# -_PSU_v2.net
KiCad netlist of a schematic drawn in EAGLE
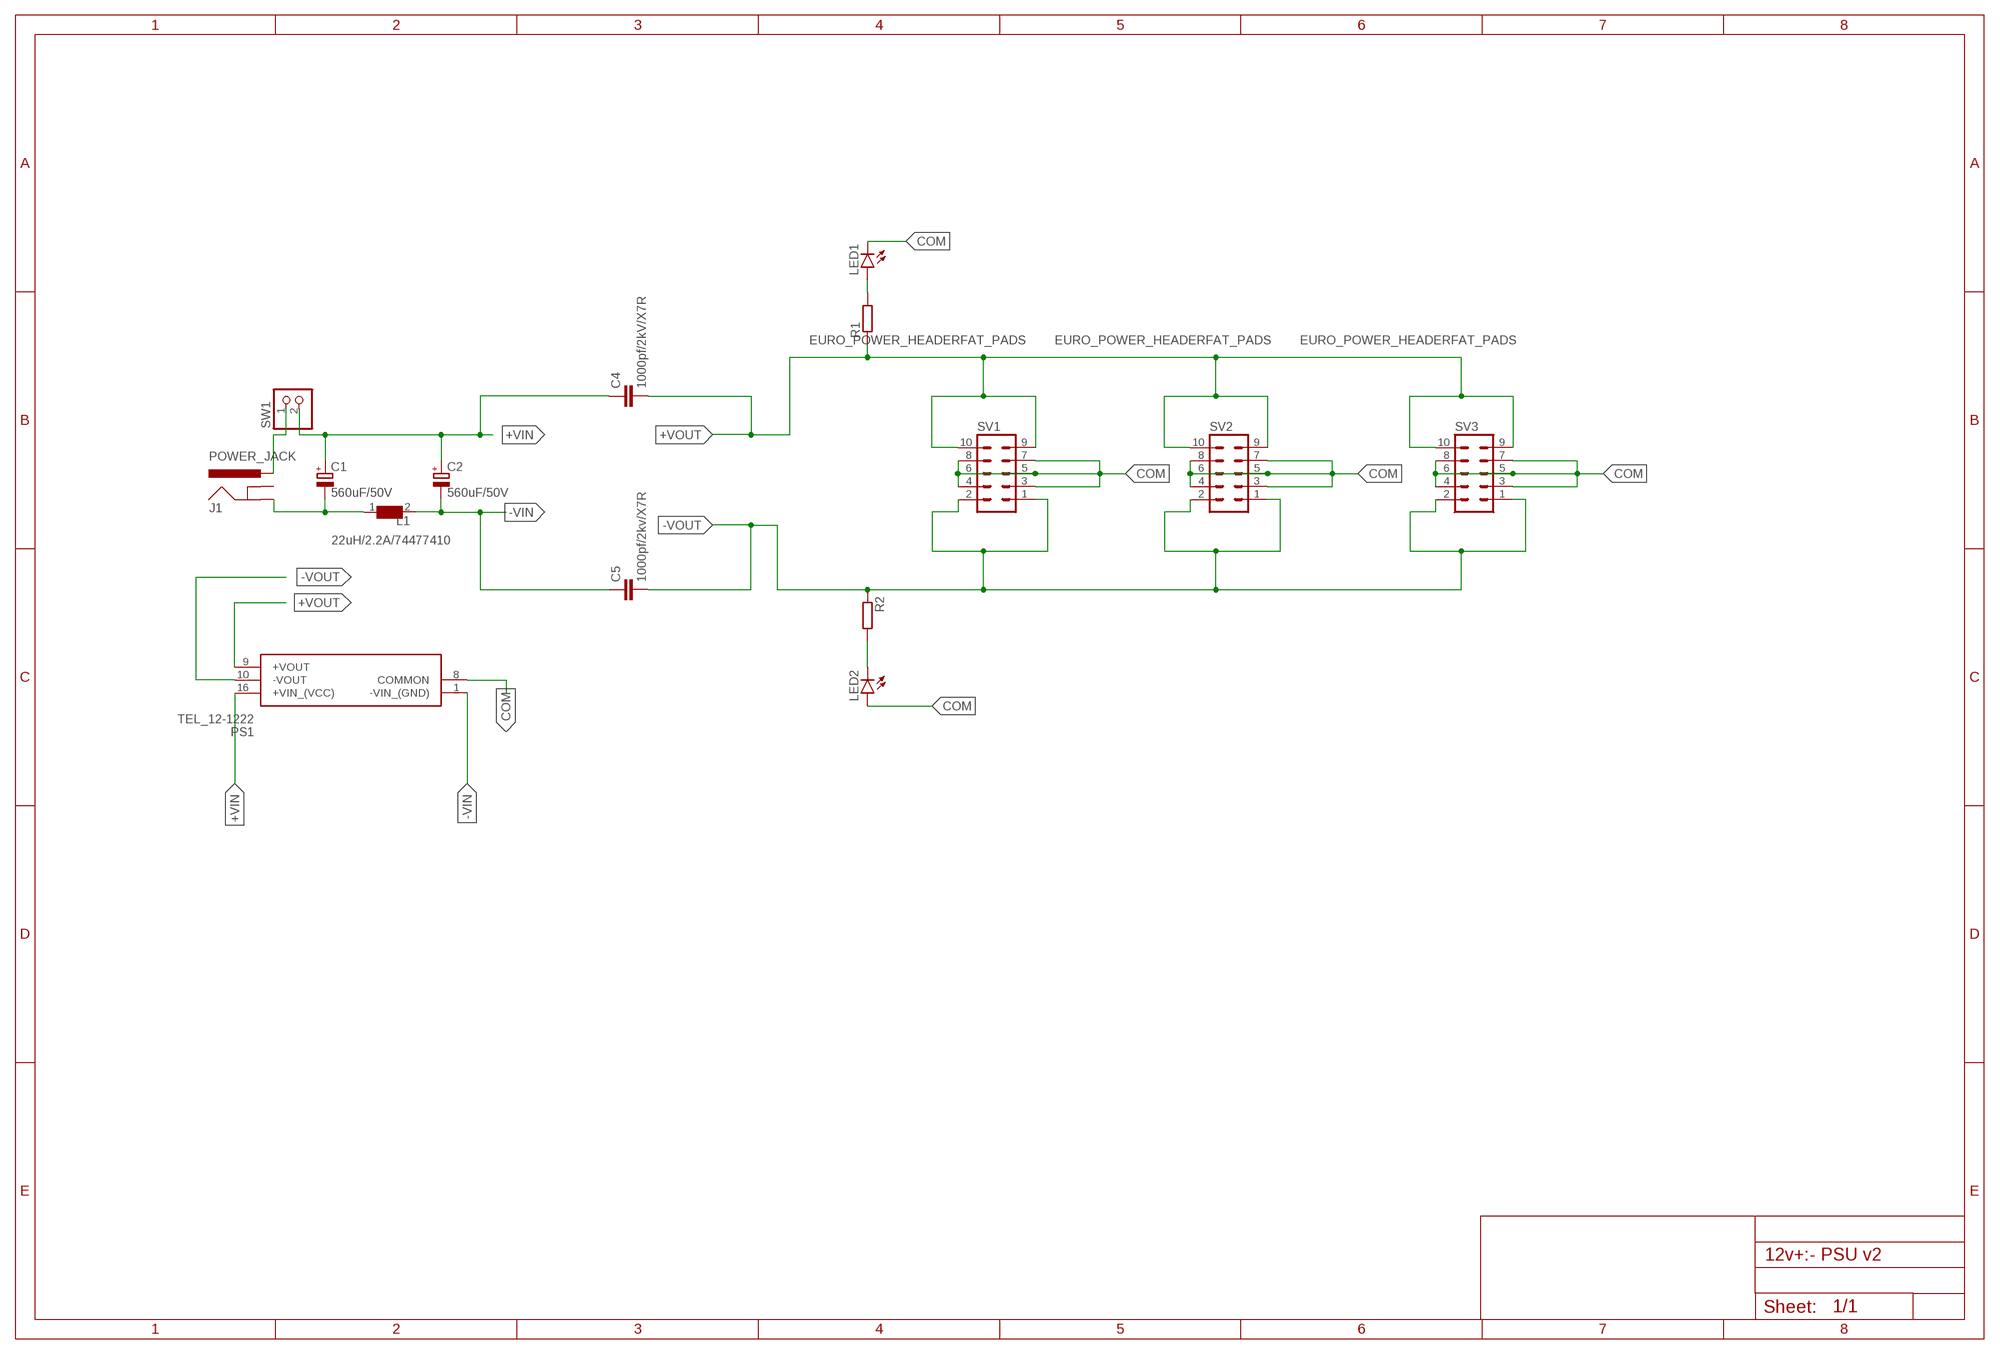
[diagram p0: schematic, sheet 1]

(export (version "E")
  (design (tool "Eeschema 10.0.6"))
  (components
    (comp (ref "C1")
      (value "560uF/50V")
      (footprint "eagle-import:E7,5-16")
      (libsource (lib "eagle-import") (part "CPOL-EUE7.5-16"))
    )
    (comp (ref "C2")
      (value "560uF/50V")
      (footprint "eagle-import:E7,5-16")
      (libsource (lib "eagle-import") (part "CPOL-EUE7.5-16"))
    )
    (comp (ref "C4")
      (value "1000pf/2kV/X7R")
      (footprint "eagle-import:C1808")
      (libsource (lib "eagle-import") (part "C-EUC1808"))
    )
    (comp (ref "C5")
      (value "1000pf/2kv/X7R")
      (footprint "eagle-import:C1808")
      (libsource (lib "eagle-import") (part "C-EUC1808"))
    )
    (comp (ref "J1")
      (value "POWER_JACK")
      (footprint "eagle-import:POWER_JACK_PTH")
      (libsource (lib "eagle-import") (part "POWER_JACK"))
    )
    (comp (ref "L1")
      (value "22uH/2.2A/74477410")
      (footprint "eagle-import:WE-PD2_5848_5820")
      (fields (field (name "MPN") "74477410"))
      (libsource (lib "eagle-import") (part "WE-PD2_5848/5820-74477410"))
    )
    (comp (ref "LED1")
      (value "LED3MM")
      (footprint "eagle-import:LED3MM")
      (libsource (lib "eagle-import") (part "LED3MM"))
    )
    (comp (ref "LED2")
      (value "LED3MM")
      (footprint "eagle-import:LED3MM")
      (libsource (lib "eagle-import") (part "LED3MM"))
    )
    (comp (ref "PS1")
      (value "TEL_12-1222")
      (footprint "eagle-import:TEL121222")
      (fields
        (field (name "MANUFACTURER_PART_NUMBER") "TEL 12-1222")
        (field (name "MOUSER_PART_NUMBER") "495-TEL12-1222")
      )
      (libsource (lib "eagle-import") (part "TEL_12-1222"))
    )
    (comp (ref "R1")
      (value "RESISTOR7MM")
      (footprint "eagle-import:7MM_RESISTOR")
      (libsource (lib "eagle-import") (part "RESISTOR7MM"))
    )
    (comp (ref "R2")
      (value "RESISTOR7MM")
      (footprint "eagle-import:7MM_RESISTOR")
      (libsource (lib "eagle-import") (part "RESISTOR7MM"))
    )
    (comp (ref "SV1")
      (value "EURO_POWER_HEADERFAT_PADS")
      (footprint "eagle-import:EURO_PWR_HEADER_FAT")
      (libsource (lib "eagle-import") (part "EURO_POWER_HEADERFAT_PADS"))
    )
    (comp (ref "SV2")
      (value "EURO_POWER_HEADERFAT_PADS")
      (footprint "eagle-import:EURO_PWR_HEADER_FAT")
      (libsource (lib "eagle-import") (part "EURO_POWER_HEADERFAT_PADS"))
    )
    (comp (ref "SV3")
      (value "EURO_POWER_HEADERFAT_PADS")
      (footprint "eagle-import:EURO_PWR_HEADER_FAT")
      (libsource (lib "eagle-import") (part "EURO_POWER_HEADERFAT_PADS"))
    )
    (comp (ref "SW1")
      (value "PINHD-1X2")
      (footprint "eagle-import:1X02")
      (libsource (lib "eagle-import") (part "PINHD-1X2"))
    )
  )
  (nets
    (net (code "1") (name "+VIN") (class "Default")
      (node (ref "C1") (pin "+") (pinfunction "+_+") (pintype "passive"))
      (node (ref "C2") (pin "+") (pinfunction "+_+") (pintype "passive"))
      (node (ref "C4") (pin "1") (pinfunction "1_1") (pintype "passive"))
      (node (ref "PS1") (pin "16") (pinfunction "+VIN_(VCC)_16") (pintype "bidirectional"))
      (node (ref "SW1") (pin "2") (pinfunction "2_2") (pintype "passive"))
    )
    (net (code "2") (name "+VOUT") (class "Default")
      (node (ref "C4") (pin "2") (pinfunction "2_2") (pintype "passive"))
      (node (ref "PS1") (pin "9") (pinfunction "+VOUT_9") (pintype "bidirectional"))
      (node (ref "R1") (pin "1") (pinfunction "1_1") (pintype "passive"))
      (node (ref "SV1") (pin "10") (pinfunction "10_10") (pintype "passive"))
      (node (ref "SV1") (pin "9") (pinfunction "9_9") (pintype "passive"))
      (node (ref "SV2") (pin "10") (pinfunction "10_10") (pintype "passive"))
      (node (ref "SV2") (pin "9") (pinfunction "9_9") (pintype "passive"))
      (node (ref "SV3") (pin "10") (pinfunction "10_10") (pintype "passive"))
      (node (ref "SV3") (pin "9") (pinfunction "9_9") (pintype "passive"))
    )
    (net (code "3") (name "-VIN") (class "Default")
      (node (ref "C2") (pin "-") (pinfunction "-_-") (pintype "passive"))
      (node (ref "C5") (pin "1") (pinfunction "1_1") (pintype "passive"))
      (node (ref "L1") (pin "2") (pinfunction "2_2") (pintype "passive"))
      (node (ref "PS1") (pin "1") (pinfunction "-VIN_(GND)_1") (pintype "bidirectional"))
    )
    (net (code "4") (name "-VOUT") (class "Default")
      (node (ref "C5") (pin "2") (pinfunction "2_2") (pintype "passive"))
      (node (ref "PS1") (pin "10") (pinfunction "-VOUT_10") (pintype "bidirectional"))
      (node (ref "R2") (pin "1") (pinfunction "1_1") (pintype "passive"))
      (node (ref "SV1") (pin "1") (pinfunction "1_1") (pintype "passive"))
      (node (ref "SV1") (pin "2") (pinfunction "2_2") (pintype "passive"))
      (node (ref "SV2") (pin "1") (pinfunction "1_1") (pintype "passive"))
      (node (ref "SV2") (pin "2") (pinfunction "2_2") (pintype "passive"))
      (node (ref "SV3") (pin "1") (pinfunction "1_1") (pintype "passive"))
      (node (ref "SV3") (pin "2") (pinfunction "2_2") (pintype "passive"))
    )
    (net (code "5") (name "COM") (class "Default")
      (node (ref "LED1") (pin "K") (pinfunction "C_K") (pintype "passive"))
      (node (ref "LED2") (pin "A") (pinfunction "A_A") (pintype "passive"))
      (node (ref "PS1") (pin "8") (pinfunction "COMMON_8") (pintype "bidirectional"))
      (node (ref "SV1") (pin "3") (pinfunction "3_3") (pintype "passive"))
      (node (ref "SV1") (pin "4") (pinfunction "4_4") (pintype "passive"))
      (node (ref "SV1") (pin "5") (pinfunction "5_5") (pintype "passive"))
      (node (ref "SV1") (pin "6") (pinfunction "6_6") (pintype "passive"))
      (node (ref "SV1") (pin "7") (pinfunction "7_7") (pintype "passive"))
      (node (ref "SV1") (pin "8") (pinfunction "8_8") (pintype "passive"))
      (node (ref "SV2") (pin "3") (pinfunction "3_3") (pintype "passive"))
      (node (ref "SV2") (pin "4") (pinfunction "4_4") (pintype "passive"))
      (node (ref "SV2") (pin "5") (pinfunction "5_5") (pintype "passive"))
      (node (ref "SV2") (pin "6") (pinfunction "6_6") (pintype "passive"))
      (node (ref "SV2") (pin "7") (pinfunction "7_7") (pintype "passive"))
      (node (ref "SV2") (pin "8") (pinfunction "8_8") (pintype "passive"))
      (node (ref "SV3") (pin "3") (pinfunction "3_3") (pintype "passive"))
      (node (ref "SV3") (pin "4") (pinfunction "4_4") (pintype "passive"))
      (node (ref "SV3") (pin "5") (pinfunction "5_5") (pintype "passive"))
      (node (ref "SV3") (pin "6") (pinfunction "6_6") (pintype "passive"))
      (node (ref "SV3") (pin "7") (pinfunction "7_7") (pintype "passive"))
      (node (ref "SV3") (pin "8") (pinfunction "8_8") (pintype "passive"))
    )
    (net (code "6") (name "Net-(C1-Pad-)") (class "Default")
      (node (ref "C1") (pin "-") (pinfunction "-_-") (pintype "passive"))
      (node (ref "J1") (pin "GND") (pinfunction "GND_GND") (pintype "bidirectional"))
      (node (ref "L1") (pin "1") (pinfunction "1_1") (pintype "passive"))
    )
    (net (code "7") (name "Net-(J1-PadPWR)") (class "Default")
      (node (ref "J1") (pin "PWR") (pinfunction "PWR_PWR") (pintype "bidirectional"))
      (node (ref "SW1") (pin "1") (pinfunction "1_1") (pintype "passive"))
    )
    (net (code "8") (name "Net-(LED1-PadA)") (class "Default")
      (node (ref "LED1") (pin "A") (pinfunction "A_A") (pintype "passive"))
      (node (ref "R1") (pin "2") (pinfunction "2_2") (pintype "passive"))
    )
    (net (code "9") (name "Net-(LED2-C)") (class "Default")
      (node (ref "LED2") (pin "K") (pinfunction "C_K") (pintype "passive"))
      (node (ref "R2") (pin "2") (pinfunction "2_2") (pintype "passive"))
    )
    (net (code "10") (name "unconnected-(J1-PadGNDBREAK)") (class "Default")
      (node (ref "J1") (pin "GNDBREAK") (pinfunction "GNDBREAK_GNDBREAK") (pintype "bidirectional"))
    )
  )
)
